# 2164_svf_breakout_planes_smd.net
KiCad netlist of a schematic drawn in EAGLE
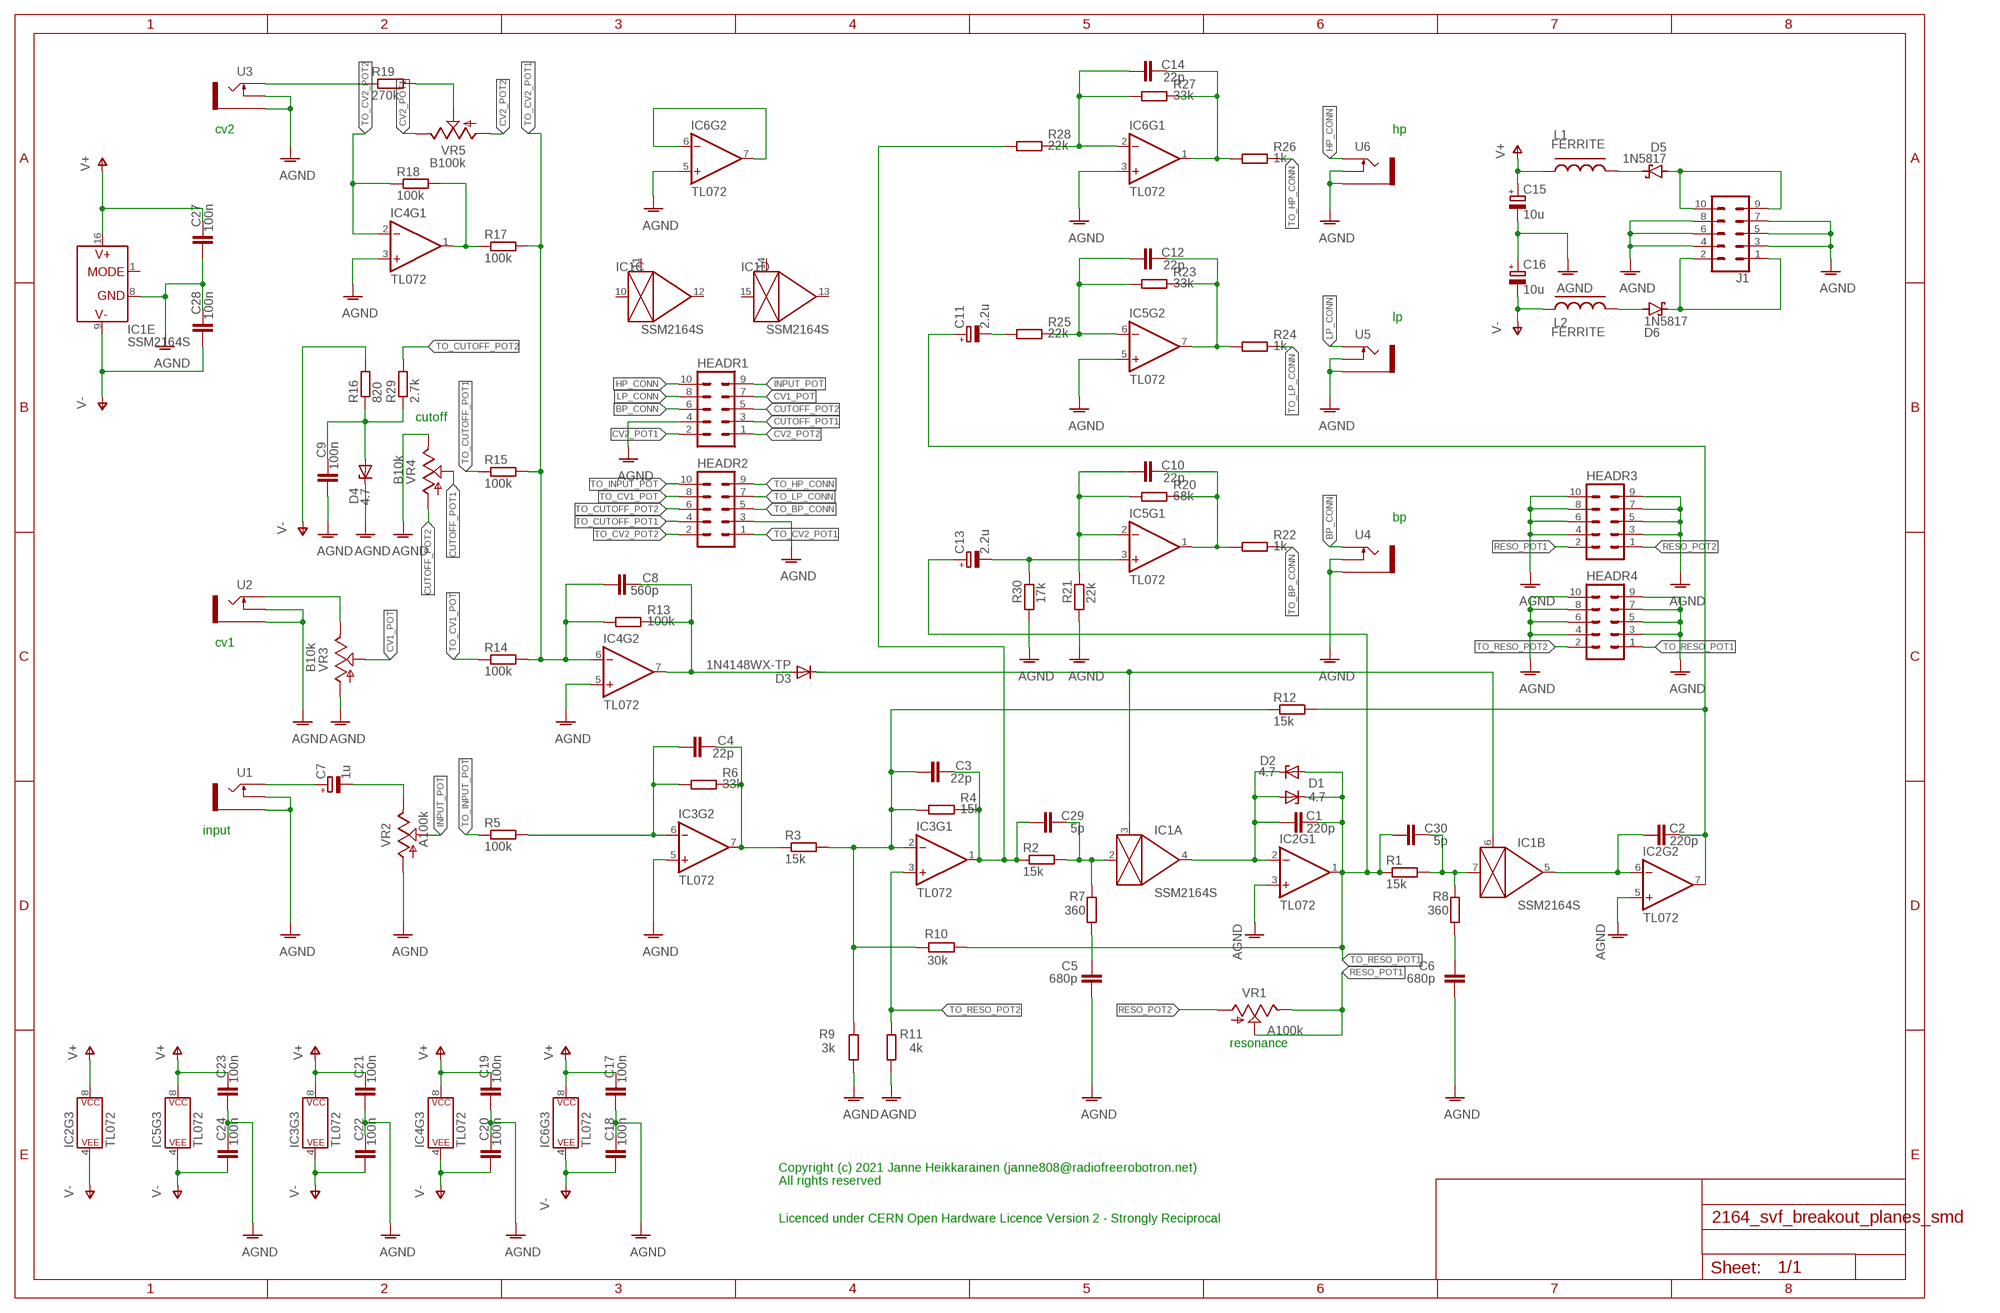
[diagram p0: schematic, sheet 1]

(export (version "E")
  (design (tool "Eeschema 10.0.6"))
  (components
    (comp (ref "C1")
      (value "220p")
      (footprint "eagle-import:C0603")
      (libsource (lib "eagle-import") (part "C-EUC0603"))
    )
    (comp (ref "C2")
      (value "220p")
      (footprint "eagle-import:C0603")
      (libsource (lib "eagle-import") (part "C-EUC0603"))
    )
    (comp (ref "C3")
      (value "22p")
      (footprint "eagle-import:C0603")
      (libsource (lib "eagle-import") (part "C-EUC0603"))
    )
    (comp (ref "C4")
      (value "22p")
      (footprint "eagle-import:C0603")
      (libsource (lib "eagle-import") (part "C-EUC0603"))
    )
    (comp (ref "C5")
      (value "680p")
      (footprint "eagle-import:C0603")
      (libsource (lib "eagle-import") (part "C-EUC0603"))
    )
    (comp (ref "C6")
      (value "680p")
      (footprint "eagle-import:C0603")
      (libsource (lib "eagle-import") (part "C-EUC0603"))
    )
    (comp (ref "C7")
      (value "1u")
      (footprint "eagle-import:PANASONIC_B")
      (libsource (lib "eagle-import") (part "CPOL-EUB"))
    )
    (comp (ref "C8")
      (value "560p")
      (footprint "eagle-import:C0603")
      (libsource (lib "eagle-import") (part "C-EUC0603"))
    )
    (comp (ref "C9")
      (value "100n")
      (footprint "eagle-import:C0603")
      (libsource (lib "eagle-import") (part "C-EUC0603"))
    )
    (comp (ref "C10")
      (value "22p")
      (footprint "eagle-import:C0603")
      (libsource (lib "eagle-import") (part "C-EUC0603"))
    )
    (comp (ref "C11")
      (value "2.2u")
      (footprint "eagle-import:PANASONIC_B")
      (libsource (lib "eagle-import") (part "CPOL-EUB"))
    )
    (comp (ref "C12")
      (value "22p")
      (footprint "eagle-import:C0603")
      (libsource (lib "eagle-import") (part "C-EUC0603"))
    )
    (comp (ref "C13")
      (value "2.2u")
      (footprint "eagle-import:PANASONIC_B")
      (libsource (lib "eagle-import") (part "CPOL-EUB"))
    )
    (comp (ref "C14")
      (value "22p")
      (footprint "eagle-import:C0603")
      (libsource (lib "eagle-import") (part "C-EUC0603"))
    )
    (comp (ref "C15")
      (value "10u")
      (footprint "eagle-import:PANASONIC_B")
      (libsource (lib "eagle-import") (part "CPOL-EUB"))
    )
    (comp (ref "C16")
      (value "10u")
      (footprint "eagle-import:PANASONIC_B")
      (libsource (lib "eagle-import") (part "CPOL-EUB"))
    )
    (comp (ref "C17")
      (value "100n")
      (footprint "eagle-import:C0603")
      (libsource (lib "eagle-import") (part "C-EUC0603"))
    )
    (comp (ref "C18")
      (value "100n")
      (footprint "eagle-import:C0603")
      (libsource (lib "eagle-import") (part "C-EUC0603"))
    )
    (comp (ref "C19")
      (value "100n")
      (footprint "eagle-import:C0603")
      (libsource (lib "eagle-import") (part "C-EUC0603"))
    )
    (comp (ref "C20")
      (value "100n")
      (footprint "eagle-import:C0603")
      (libsource (lib "eagle-import") (part "C-EUC0603"))
    )
    (comp (ref "C21")
      (value "100n")
      (footprint "eagle-import:C0603")
      (libsource (lib "eagle-import") (part "C-EUC0603"))
    )
    (comp (ref "C22")
      (value "100n")
      (footprint "eagle-import:C0603")
      (libsource (lib "eagle-import") (part "C-EUC0603"))
    )
    (comp (ref "C23")
      (value "100n")
      (footprint "eagle-import:C0603")
      (libsource (lib "eagle-import") (part "C-EUC0603"))
    )
    (comp (ref "C24")
      (value "100n")
      (footprint "eagle-import:C0603")
      (libsource (lib "eagle-import") (part "C-EUC0603"))
    )
    (comp (ref "C27")
      (value "100n")
      (footprint "eagle-import:C0603")
      (libsource (lib "eagle-import") (part "C-EUC0603"))
    )
    (comp (ref "C28")
      (value "100n")
      (footprint "eagle-import:C0603")
      (libsource (lib "eagle-import") (part "C-EUC0603"))
    )
    (comp (ref "C29")
      (value "5p")
      (footprint "eagle-import:C0603")
      (libsource (lib "eagle-import") (part "C-EUC0603"))
    )
    (comp (ref "C30")
      (value "5p")
      (footprint "eagle-import:C0603")
      (libsource (lib "eagle-import") (part "C-EUC0603"))
    )
    (comp (ref "D1")
      (value "4.7")
      (footprint "eagle-import:DIODE_SOD80C")
      (libsource (lib "eagle-import") (part "DIODE_ZENER-DIODESOD80C"))
    )
    (comp (ref "D2")
      (value "4.7")
      (footprint "eagle-import:DIODE_SOD80C")
      (libsource (lib "eagle-import") (part "DIODE_ZENER-DIODESOD80C"))
    )
    (comp (ref "D3")
      (value "1N4148WX-TP")
      (footprint "eagle-import:SOD323R-INFINEON")
      (libsource (lib "eagle-import") (part "1N4148WX-TP"))
    )
    (comp (ref "D4")
      (value "4.7")
      (footprint "eagle-import:DIODE_SOD80C")
      (libsource (lib "eagle-import") (part "DIODE_ZENER-DIODESOD80C"))
    )
    (comp (ref "D5")
      (value "1N5817")
      (footprint "eagle-import:DO35-7")
      (libsource (lib "eagle-import") (part "SCHOTTKY-DIODEDO35-7"))
    )
    (comp (ref "D6")
      (value "1N5817")
      (footprint "eagle-import:DO35-7")
      (libsource (lib "eagle-import") (part "SCHOTTKY-DIODEDO35-7"))
    )
    (comp (ref "HEADR1")
      (value "10PIN_BACKSIDE")
      (footprint "eagle-import:10PIN_BACKSIDE")
      (libsource (lib "eagle-import") (part "10PIN_BACKSIDE"))
    )
    (comp (ref "HEADR2")
      (value "10PIN_BACKSIDE")
      (footprint "eagle-import:10PIN_BACKSIDE")
      (libsource (lib "eagle-import") (part "10PIN_BACKSIDE"))
    )
    (comp (ref "HEADR3")
      (value "10PIN_BACKSIDE")
      (footprint "eagle-import:10PIN_BACKSIDE")
      (libsource (lib "eagle-import") (part "10PIN_BACKSIDE"))
    )
    (comp (ref "HEADR4")
      (value "10PIN_BACKSIDE")
      (footprint "eagle-import:10PIN_BACKSIDE")
      (libsource (lib "eagle-import") (part "10PIN_BACKSIDE"))
    )
    (comp (ref "IC1")
      (value "SSM2164S")
      (footprint "eagle-import:SOIC16N")
      (libsource (lib "eagle-import") (part "SSM2164S"))
    )
    (comp (ref "IC2")
      (value "TL072")
      (footprint "eagle-import:SO08")
      (libsource (lib "eagle-import") (part "OPAMP-DUALU"))
    )
    (comp (ref "IC3")
      (value "TL072")
      (footprint "eagle-import:SO08")
      (libsource (lib "eagle-import") (part "OPAMP-DUALU"))
    )
    (comp (ref "IC4")
      (value "TL072")
      (footprint "eagle-import:SO08")
      (libsource (lib "eagle-import") (part "OPAMP-DUALU"))
    )
    (comp (ref "IC5")
      (value "TL072")
      (footprint "eagle-import:SO08")
      (libsource (lib "eagle-import") (part "OPAMP-DUALU"))
    )
    (comp (ref "IC6")
      (value "TL072")
      (footprint "eagle-import:SO08")
      (libsource (lib "eagle-import") (part "OPAMP-DUALU"))
    )
    (comp (ref "J1")
      (value "CONN_05X2SHD")
      (footprint "eagle-import:2X5-SHROUDED")
      (libsource (lib "eagle-import") (part "CONN_05X2SHD"))
    )
    (comp (ref "L1")
      (value "FERRITE")
      (footprint "eagle-import:0603")
      (fields (field (name "PARTNO") "?"))
      (libsource (lib "eagle-import") (part "EXC3BP"))
    )
    (comp (ref "L2")
      (value "FERRITE")
      (footprint "eagle-import:0603")
      (fields (field (name "PARTNO") "?"))
      (libsource (lib "eagle-import") (part "EXC3BP"))
    )
    (comp (ref "R1")
      (value "15k")
      (footprint "eagle-import:R0603")
      (libsource (lib "eagle-import") (part "R-EU_R0603"))
    )
    (comp (ref "R2")
      (value "15k")
      (footprint "eagle-import:R0603")
      (libsource (lib "eagle-import") (part "R-EU_R0603"))
    )
    (comp (ref "R3")
      (value "15k")
      (footprint "eagle-import:R0603")
      (libsource (lib "eagle-import") (part "R-EU_R0603"))
    )
    (comp (ref "R4")
      (value "15k")
      (footprint "eagle-import:R0603")
      (libsource (lib "eagle-import") (part "R-EU_R0603"))
    )
    (comp (ref "R5")
      (value "100k")
      (footprint "eagle-import:R0603")
      (libsource (lib "eagle-import") (part "R-EU_R0603"))
    )
    (comp (ref "R6")
      (value "33k")
      (footprint "eagle-import:R0603")
      (libsource (lib "eagle-import") (part "R-EU_R0603"))
    )
    (comp (ref "R7")
      (value "360")
      (footprint "eagle-import:R0603")
      (libsource (lib "eagle-import") (part "R-EU_R0603"))
    )
    (comp (ref "R8")
      (value "360")
      (footprint "eagle-import:R0603")
      (libsource (lib "eagle-import") (part "R-EU_R0603"))
    )
    (comp (ref "R9")
      (value "3k")
      (footprint "eagle-import:R0603")
      (libsource (lib "eagle-import") (part "R-EU_R0603"))
    )
    (comp (ref "R10")
      (value "30k")
      (footprint "eagle-import:R0603")
      (libsource (lib "eagle-import") (part "R-EU_R0603"))
    )
    (comp (ref "R11")
      (value "4k")
      (footprint "eagle-import:R0603")
      (libsource (lib "eagle-import") (part "R-EU_R0603"))
    )
    (comp (ref "R12")
      (value "15k")
      (footprint "eagle-import:R0603")
      (libsource (lib "eagle-import") (part "R-EU_R0603"))
    )
    (comp (ref "R13")
      (value "100k")
      (footprint "eagle-import:R0603")
      (libsource (lib "eagle-import") (part "R-EU_R0603"))
    )
    (comp (ref "R14")
      (value "100k")
      (footprint "eagle-import:R0603")
      (libsource (lib "eagle-import") (part "R-EU_R0603"))
    )
    (comp (ref "R15")
      (value "100k")
      (footprint "eagle-import:R0603")
      (libsource (lib "eagle-import") (part "R-EU_R0603"))
    )
    (comp (ref "R16")
      (value "820")
      (footprint "eagle-import:R0603")
      (libsource (lib "eagle-import") (part "R-EU_R0603"))
    )
    (comp (ref "R17")
      (value "100k")
      (footprint "eagle-import:R0603")
      (libsource (lib "eagle-import") (part "R-EU_R0603"))
    )
    (comp (ref "R18")
      (value "100k")
      (footprint "eagle-import:R0603")
      (libsource (lib "eagle-import") (part "R-EU_R0603"))
    )
    (comp (ref "R19")
      (value "270k")
      (footprint "eagle-import:R0603")
      (libsource (lib "eagle-import") (part "R-EU_R0603"))
    )
    (comp (ref "R20")
      (value "68k")
      (footprint "eagle-import:R0603")
      (libsource (lib "eagle-import") (part "R-EU_R0603"))
    )
    (comp (ref "R21")
      (value "22k")
      (footprint "eagle-import:R0603")
      (libsource (lib "eagle-import") (part "R-EU_R0603"))
    )
    (comp (ref "R22")
      (value "1k")
      (footprint "eagle-import:R0603")
      (libsource (lib "eagle-import") (part "R-EU_R0603"))
    )
    (comp (ref "R23")
      (value "33k")
      (footprint "eagle-import:R0603")
      (libsource (lib "eagle-import") (part "R-EU_R0603"))
    )
    (comp (ref "R24")
      (value "1k")
      (footprint "eagle-import:R0603")
      (libsource (lib "eagle-import") (part "R-EU_R0603"))
    )
    (comp (ref "R25")
      (value "22k")
      (footprint "eagle-import:R0603")
      (libsource (lib "eagle-import") (part "R-EU_R0603"))
    )
    (comp (ref "R26")
      (value "1k")
      (footprint "eagle-import:R0603")
      (libsource (lib "eagle-import") (part "R-EU_R0603"))
    )
    (comp (ref "R27")
      (value "33k")
      (footprint "eagle-import:R0603")
      (libsource (lib "eagle-import") (part "R-EU_R0603"))
    )
    (comp (ref "R28")
      (value "22k")
      (footprint "eagle-import:R0603")
      (libsource (lib "eagle-import") (part "R-EU_R0603"))
    )
    (comp (ref "R29")
      (value "2.7k")
      (footprint "eagle-import:R0603")
      (libsource (lib "eagle-import") (part "R-EU_R0603"))
    )
    (comp (ref "R30")
      (value "17k")
      (footprint "eagle-import:R0603")
      (libsource (lib "eagle-import") (part "R-EU_R0603"))
    )
    (comp (ref "U1")
      (value "THONKICONNNEW")
      (footprint "eagle-import:WQP-PJ301M-12_JACK")
      (libsource (lib "eagle-import") (part "THONKICONNNEW"))
    )
    (comp (ref "U2")
      (value "THONKICONNNEW")
      (footprint "eagle-import:WQP-PJ301M-12_JACK")
      (libsource (lib "eagle-import") (part "THONKICONNNEW"))
    )
    (comp (ref "U3")
      (value "THONKICONNNEW")
      (footprint "eagle-import:WQP-PJ301M-12_JACK")
      (libsource (lib "eagle-import") (part "THONKICONNNEW"))
    )
    (comp (ref "U4")
      (value "THONKICONNNEW")
      (footprint "eagle-import:WQP-PJ301M-12_JACK")
      (libsource (lib "eagle-import") (part "THONKICONNNEW"))
    )
    (comp (ref "U5")
      (value "THONKICONNNEW")
      (footprint "eagle-import:WQP-PJ301M-12_JACK")
      (libsource (lib "eagle-import") (part "THONKICONNNEW"))
    )
    (comp (ref "U6")
      (value "THONKICONNNEW")
      (footprint "eagle-import:WQP-PJ301M-12_JACK")
      (libsource (lib "eagle-import") (part "THONKICONNNEW"))
    )
    (comp (ref "VR1")
      (value "A100k")
      (footprint "eagle-import:9MM_SNAP-IN_POT")
      (libsource (lib "eagle-import") (part "9MM_SNAP-IN_POT_"))
    )
    (comp (ref "VR2")
      (value "A100k")
      (footprint "eagle-import:9MM_SNAP-IN_POT")
      (libsource (lib "eagle-import") (part "9MM_SNAP-IN_POT_"))
    )
    (comp (ref "VR3")
      (value "B10k")
      (footprint "eagle-import:9MM_SNAP-IN_POT")
      (libsource (lib "eagle-import") (part "9MM_SNAP-IN_POT_"))
    )
    (comp (ref "VR4")
      (value "B10k")
      (footprint "eagle-import:9MM_SNAP-IN_POT")
      (libsource (lib "eagle-import") (part "9MM_SNAP-IN_POT_"))
    )
    (comp (ref "VR5")
      (value "B100k")
      (footprint "eagle-import:9MM_SNAP-IN_POT")
      (libsource (lib "eagle-import") (part "9MM_SNAP-IN_POT_"))
    )
  )
  (nets
    (net (code "1") (name "AGND") (class "Default")
      (node (ref "C15") (pin "-") (pinfunction "-_-") (pintype "passive"))
      (node (ref "C16") (pin "+") (pinfunction "+_+") (pintype "passive"))
      (node (ref "C17") (pin "1") (pinfunction "1_1") (pintype "passive"))
      (node (ref "C18") (pin "2") (pinfunction "2_2") (pintype "passive"))
      (node (ref "C19") (pin "1") (pinfunction "1_1") (pintype "passive"))
      (node (ref "C20") (pin "2") (pinfunction "2_2") (pintype "passive"))
      (node (ref "C21") (pin "1") (pinfunction "1_1") (pintype "passive"))
      (node (ref "C22") (pin "2") (pinfunction "2_2") (pintype "passive"))
      (node (ref "C23") (pin "1") (pinfunction "1_1") (pintype "passive"))
      (node (ref "C24") (pin "2") (pinfunction "2_2") (pintype "passive"))
      (node (ref "C27") (pin "1") (pinfunction "1_1") (pintype "passive"))
      (node (ref "C28") (pin "2") (pinfunction "2_2") (pintype "passive"))
      (node (ref "C5") (pin "1") (pinfunction "1_1") (pintype "passive"))
      (node (ref "C6") (pin "1") (pinfunction "1_1") (pintype "passive"))
      (node (ref "C9") (pin "1") (pinfunction "1_1") (pintype "passive"))
      (node (ref "D4") (pin "C") (pinfunction "C_C") (pintype "passive"))
      (node (ref "HEADR1") (pin "4") (pinfunction "4_4") (pintype "passive"))
      (node (ref "HEADR2") (pin "3") (pinfunction "3_3") (pintype "passive"))
      (node (ref "HEADR3") (pin "10") (pinfunction "10_10") (pintype "passive"))
      (node (ref "HEADR3") (pin "3") (pinfunction "3_3") (pintype "passive"))
      (node (ref "HEADR3") (pin "4") (pinfunction "4_4") (pintype "passive"))
      (node (ref "HEADR3") (pin "5") (pinfunction "5_5") (pintype "passive"))
      (node (ref "HEADR3") (pin "6") (pinfunction "6_6") (pintype "passive"))
      (node (ref "HEADR3") (pin "7") (pinfunction "7_7") (pintype "passive"))
      (node (ref "HEADR3") (pin "8") (pinfunction "8_8") (pintype "passive"))
      (node (ref "HEADR3") (pin "9") (pinfunction "9_9") (pintype "passive"))
      (node (ref "HEADR4") (pin "10") (pinfunction "10_10") (pintype "passive"))
      (node (ref "HEADR4") (pin "3") (pinfunction "3_3") (pintype "passive"))
      (node (ref "HEADR4") (pin "4") (pinfunction "4_4") (pintype "passive"))
      (node (ref "HEADR4") (pin "5") (pinfunction "5_5") (pintype "passive"))
      (node (ref "HEADR4") (pin "6") (pinfunction "6_6") (pintype "passive"))
      (node (ref "HEADR4") (pin "7") (pinfunction "7_7") (pintype "passive"))
      (node (ref "HEADR4") (pin "8") (pinfunction "8_8") (pintype "passive"))
      (node (ref "HEADR4") (pin "9") (pinfunction "9_9") (pintype "passive"))
      (node (ref "IC1") (pin "8") (pinfunction "GND_8") (pintype "power_in"))
      (node (ref "IC2") (pin "3") (pinfunction "+IN_3") (pintype "input"))
      (node (ref "IC2") (pin "5") (pinfunction "+IN_5") (pintype "input"))
      (node (ref "IC3") (pin "5") (pinfunction "+IN_5") (pintype "input"))
      (node (ref "IC4") (pin "3") (pinfunction "+IN_3") (pintype "input"))
      (node (ref "IC4") (pin "5") (pinfunction "+IN_5") (pintype "input"))
      (node (ref "IC5") (pin "5") (pinfunction "+IN_5") (pintype "input"))
      (node (ref "IC6") (pin "3") (pinfunction "+IN_3") (pintype "input"))
      (node (ref "IC6") (pin "5") (pinfunction "+IN_5") (pintype "input"))
      (node (ref "J1") (pin "3") (pinfunction "3_3") (pintype "passive"))
      (node (ref "J1") (pin "4") (pinfunction "4_4") (pintype "passive"))
      (node (ref "J1") (pin "5") (pinfunction "5_5") (pintype "passive"))
      (node (ref "J1") (pin "6") (pinfunction "6_6") (pintype "passive"))
      (node (ref "J1") (pin "7") (pinfunction "7_7") (pintype "passive"))
      (node (ref "J1") (pin "8") (pinfunction "8_8") (pintype "passive"))
      (node (ref "R11") (pin "1") (pinfunction "1_1") (pintype "passive"))
      (node (ref "R21") (pin "1") (pinfunction "1_1") (pintype "passive"))
      (node (ref "R30") (pin "1") (pinfunction "1_1") (pintype "passive"))
      (node (ref "R9") (pin "1") (pinfunction "1_1") (pintype "passive"))
      (node (ref "U1") (pin "P$2_SWITCH") (pinfunction "SWITCH_P$2_SWITCH") (pintype "passive"))
      (node (ref "U1") (pin "P$3_SLEEVE") (pinfunction "SLEEVE_P$3_SLEEVE") (pintype "passive"))
      (node (ref "U2") (pin "P$2_SWITCH") (pinfunction "SWITCH_P$2_SWITCH") (pintype "passive"))
      (node (ref "U2") (pin "P$3_SLEEVE") (pinfunction "SLEEVE_P$3_SLEEVE") (pintype "passive"))
      (node (ref "U3") (pin "P$2_SWITCH") (pinfunction "SWITCH_P$2_SWITCH") (pintype "passive"))
      (node (ref "U3") (pin "P$3_SLEEVE") (pinfunction "SLEEVE_P$3_SLEEVE") (pintype "passive"))
      (node (ref "U4") (pin "P$2_SWITCH") (pinfunction "SWITCH_P$2_SWITCH") (pintype "passive"))
      (node (ref "U4") (pin "P$3_SLEEVE") (pinfunction "SLEEVE_P$3_SLEEVE") (pintype "passive"))
      (node (ref "U5") (pin "P$2_SWITCH") (pinfunction "SWITCH_P$2_SWITCH") (pintype "passive"))
      (node (ref "U5") (pin "P$3_SLEEVE") (pinfunction "SLEEVE_P$3_SLEEVE") (pintype "passive"))
      (node (ref "U6") (pin "P$2_SWITCH") (pinfunction "SWITCH_P$2_SWITCH") (pintype "passive"))
      (node (ref "U6") (pin "P$3_SLEEVE") (pinfunction "SLEEVE_P$3_SLEEVE") (pintype "passive"))
      (node (ref "VR2") (pin "1") (pinfunction "A_1") (pintype "passive"))
      (node (ref "VR3") (pin "1") (pinfunction "A_1") (pintype "passive"))
      (node (ref "VR4") (pin "3") (pinfunction "E_3") (pintype "passive"))
    )
    (net (code "2") (name "BP_CONN") (class "Default")
      (node (ref "HEADR1") (pin "6") (pinfunction "6_6") (pintype "passive"))
      (node (ref "U4") (pin "P$1_TIP") (pinfunction "TIP_P$1_TIP") (pintype "passive"))
    )
    (net (code "3") (name "CUTOFF_POT1") (class "Default")
      (node (ref "HEADR1") (pin "3") (pinfunction "3_3") (pintype "passive"))
      (node (ref "VR4") (pin "2") (pinfunction "S_2") (pintype "passive"))
    )
    (net (code "4") (name "CUTOFF_POT2") (class "Default")
      (node (ref "HEADR1") (pin "5") (pinfunction "5_5") (pintype "passive"))
      (node (ref "VR4") (pin "1") (pinfunction "A_1") (pintype "passive"))
    )
    (net (code "5") (name "CV1_POT") (class "Default")
      (node (ref "HEADR1") (pin "7") (pinfunction "7_7") (pintype "passive"))
      (node (ref "VR3") (pin "2") (pinfunction "S_2") (pintype "passive"))
    )
    (net (code "6") (name "CV2_POT1") (class "Default")
      (node (ref "HEADR1") (pin "2") (pinfunction "2_2") (pintype "passive"))
      (node (ref "VR5") (pin "3") (pinfunction "E_3") (pintype "passive"))
    )
    (net (code "7") (name "CV2_POT2") (class "Default")
      (node (ref "HEADR1") (pin "1") (pinfunction "1_1") (pintype "passive"))
      (node (ref "VR5") (pin "1") (pinfunction "A_1") (pintype "passive"))
    )
    (net (code "8") (name "HP_CONN") (class "Default")
      (node (ref "HEADR1") (pin "10") (pinfunction "10_10") (pintype "passive"))
      (node (ref "U6") (pin "P$1_TIP") (pinfunction "TIP_P$1_TIP") (pintype "passive"))
    )
    (net (code "9") (name "INPUT_POT") (class "Default")
      (node (ref "HEADR1") (pin "9") (pinfunction "9_9") (pintype "passive"))
      (node (ref "VR2") (pin "2") (pinfunction "S_2") (pintype "passive"))
    )
    (net (code "10") (name "LP_CONN") (class "Default")
      (node (ref "HEADR1") (pin "8") (pinfunction "8_8") (pintype "passive"))
      (node (ref "U5") (pin "P$1_TIP") (pinfunction "TIP_P$1_TIP") (pintype "passive"))
    )
    (net (code "11") (name "Net-(C5-Pad2)") (class "Default")
      (node (ref "C5") (pin "2") (pinfunction "2_2") (pintype "passive"))
      (node (ref "R7") (pin "1") (pinfunction "1_1") (pintype "passive"))
    )
    (net (code "12") (name "Net-(C6-Pad2)") (class "Default")
      (node (ref "C6") (pin "2") (pinfunction "2_2") (pintype "passive"))
      (node (ref "R8") (pin "1") (pinfunction "1_1") (pintype "passive"))
    )
    (net (code "13") (name "Net-(C9-Pad2)") (class "Default")
      (node (ref "C9") (pin "2") (pinfunction "2_2") (pintype "passive"))
      (node (ref "D4") (pin "A") (pinfunction "A_A") (pintype "passive"))
      (node (ref "R16") (pin "1") (pinfunction "1_1") (pintype "passive"))
      (node (ref "R29") (pin "1") (pinfunction "1_1") (pintype "passive"))
    )
    (net (code "14") (name "Net-(C11-Pad-)") (class "Default")
      (node (ref "C11") (pin "-") (pinfunction "-_-") (pintype "passive"))
      (node (ref "R25") (pin "1") (pinfunction "1_1") (pintype "passive"))
    )
    (net (code "15") (name "Net-(D5-PadA)") (class "Default")
      (node (ref "D5") (pin "A") (pinfunction "A_A") (pintype "passive"))
      (node (ref "J1") (pin "10") (pinfunction "10_10") (pintype "passive"))
      (node (ref "J1") (pin "9") (pinfunction "9_9") (pintype "passive"))
    )
    (net (code "16") (name "Net-(D5-PadC)") (class "Default")
      (node (ref "D5") (pin "C") (pinfunction "C_C") (pintype "passive"))
      (node (ref "L1") (pin "2") (pinfunction "2_2") (pintype "passive"))
    )
    (net (code "17") (name "Net-(D6-PadA)") (class "Default")
      (node (ref "D6") (pin "A") (pinfunction "A_A") (pintype "passive"))
      (node (ref "L2") (pin "2") (pinfunction "2_2") (pintype "passive"))
    )
    (net (code "18") (name "Net-(D6-PadC)") (class "Default")
      (node (ref "D6") (pin "C") (pinfunction "C_C") (pintype "passive"))
      (node (ref "J1") (pin "1") (pinfunction "1_1") (pintype "passive"))
      (node (ref "J1") (pin "2") (pinfunction "2_2") (pintype "passive"))
    )
    (net (code "19") (name "Net-(IC1A-CTRL)") (class "Default")
      (node (ref "D3") (pin "C") (pinfunction "C_C") (pintype "passive"))
      (node (ref "IC1") (pin "3") (pinfunction "CTRL_3") (pintype "input"))
      (node (ref "IC1") (pin "6") (pinfunction "CTRL_6") (pintype "input"))
    )
    (net (code "20") (name "Net-(IC1A-IN)") (class "Default")
      (node (ref "C29") (pin "2") (pinfunction "2_2") (pintype "passive"))
      (node (ref "IC1") (pin "2") (pinfunction "IN_2") (pintype "input"))
      (node (ref "R2") (pin "2") (pinfunction "2_2") (pintype "passive"))
      (node (ref "R7") (pin "2") (pinfunction "2_2") (pintype "passive"))
    )
    (net (code "21") (name "Net-(IC1A-OUT)") (class "Default")
      (node (ref "C1") (pin "1") (pinfunction "1_1") (pintype "passive"))
      (node (ref "D1") (pin "A") (pinfunction "A_A") (pintype "passive"))
      (node (ref "D2") (pin "C") (pinfunction "C_C") (pintype "passive"))
      (node (ref "IC1") (pin "4") (pinfunction "OUT_4") (pintype "output"))
      (node (ref "IC2") (pin "2") (pinfunction "-IN_2") (pintype "input"))
    )
    (net (code "22") (name "Net-(IC1B-IN)") (class "Default")
      (node (ref "C30") (pin "2") (pinfunction "2_2") (pintype "passive"))
      (node (ref "IC1") (pin "7") (pinfunction "IN_7") (pintype "input"))
      (node (ref "R1") (pin "2") (pinfunction "2_2") (pintype "passive"))
      (node (ref "R8") (pin "2") (pinfunction "2_2") (pintype "passive"))
    )
    (net (code "23") (name "Net-(IC1B-OUT)") (class "Default")
      (node (ref "C2") (pin "1") (pinfunction "1_1") (pintype "passive"))
      (node (ref "IC1") (pin "5") (pinfunction "OUT_5") (pintype "output"))
      (node (ref "IC2") (pin "6") (pinfunction "-IN_6") (pintype "input"))
    )
    (net (code "24") (name "Net-(IC2B-OUT)") (class "Default")
      (node (ref "C11") (pin "+") (pinfunction "+_+") (pintype "passive"))
      (node (ref "C2") (pin "2") (pinfunction "2_2") (pintype "passive"))
      (node (ref "IC2") (pin "7") (pinfunction "OUT_7") (pintype "output"))
      (node (ref "R12") (pin "2") (pinfunction "2_2") (pintype "passive"))
    )
    (net (code "25") (name "Net-(IC3A--IN)") (class "Default")
      (node (ref "C3") (pin "1") (pinfunction "1_1") (pintype "passive"))
      (node (ref "IC3") (pin "2") (pinfunction "-IN_2") (pintype "input"))
      (node (ref "R10") (pin "2") (pinfunction "2_2") (pintype "passive"))
      (node (ref "R12") (pin "1") (pinfunction "1_1") (pintype "passive"))
      (node (ref "R3") (pin "2") (pinfunction "2_2") (pintype "passive"))
      (node (ref "R4") (pin "1") (pinfunction "1_1") (pintype "passive"))
      (node (ref "R9") (pin "2") (pinfunction "2_2") (pintype "passive"))
    )
    (net (code "26") (name "Net-(IC3A-OUT)") (class "Default")
      (node (ref "C29") (pin "1") (pinfunction "1_1") (pintype "passive"))
      (node (ref "C3") (pin "2") (pinfunction "2_2") (pintype "passive"))
      (node (ref "IC3") (pin "1") (pinfunction "OUT_1") (pintype "output"))
      (node (ref "R2") (pin "1") (pinfunction "1_1") (pintype "passive"))
      (node (ref "R28") (pin "1") (pinfunction "1_1") (pintype "passive"))
      (node (ref "R4") (pin "2") (pinfunction "2_2") (pintype "passive"))
    )
    (net (code "27") (name "Net-(IC3B--IN)") (class "Default")
      (node (ref "C4") (pin "1") (pinfunction "1_1") (pintype "passive"))
      (node (ref "IC3") (pin "6") (pinfunction "-IN_6") (pintype "input"))
      (node (ref "R5") (pin "2") (pinfunction "2_2") (pintype "passive"))
      (node (ref "R6") (pin "1") (pinfunction "1_1") (pintype "passive"))
    )
    (net (code "28") (name "Net-(IC3B-OUT)") (class "Default")
      (node (ref "C4") (pin "2") (pinfunction "2_2") (pintype "passive"))
      (node (ref "IC3") (pin "7") (pinfunction "OUT_7") (pintype "output"))
      (node (ref "R3") (pin "1") (pinfunction "1_1") (pintype "passive"))
      (node (ref "R6") (pin "2") (pinfunction "2_2") (pintype "passive"))
    )
    (net (code "29") (name "Net-(IC4A-OUT)") (class "Default")
      (node (ref "IC4") (pin "1") (pinfunction "OUT_1") (pintype "output"))
      (node (ref "R17") (pin "1") (pinfunction "1_1") (pintype "passive"))
      (node (ref "R18") (pin "2") (pinfunction "2_2") (pintype "passive"))
    )
    (net (code "30") (name "Net-(IC4B-OUT)") (class "Default")
      (node (ref "C8") (pin "2") (pinfunction "2_2") (pintype "passive"))
      (node (ref "D3") (pin "A") (pinfunction "A_A") (pintype "passive"))
      (node (ref "IC4") (pin "7") (pinfunction "OUT_7") (pintype "output"))
      (node (ref "R13") (pin "2") (pinfunction "2_2") (pintype "passive"))
    )
    (net (code "31") (name "Net-(IC5A-+IN)") (class "Default")
      (node (ref "C13") (pin "-") (pinfunction "-_-") (pintype "passive"))
      (node (ref "IC5") (pin "3") (pinfunction "+IN_3") (pintype "input"))
      (node (ref "R30") (pin "2") (pinfunction "2_2") (pintype "passive"))
    )
    (net (code "32") (name "Net-(IC5A--IN)") (class "Default")
      (node (ref "C10") (pin "1") (pinfunction "1_1") (pintype "passive"))
      (node (ref "IC5") (pin "2") (pinfunction "-IN_2") (pintype "input"))
      (node (ref "R20") (pin "1") (pinfunction "1_1") (pintype "passive"))
      (node (ref "R21") (pin "2") (pinfunction "2_2") (pintype "passive"))
    )
    (net (code "33") (name "Net-(IC5A-OUT)") (class "Default")
      (node (ref "C10") (pin "2") (pinfunction "2_2") (pintype "passive"))
      (node (ref "IC5") (pin "1") (pinfunction "OUT_1") (pintype "output"))
      (node (ref "R20") (pin "2") (pinfunction "2_2") (pintype "passive"))
      (node (ref "R22") (pin "1") (pinfunction "1_1") (pintype "passive"))
    )
    (net (code "34") (name "Net-(IC5B--IN)") (class "Default")
      (node (ref "C12") (pin "1") (pinfunction "1_1") (pintype "passive"))
      (node (ref "IC5") (pin "6") (pinfunction "-IN_6") (pintype "input"))
      (node (ref "R23") (pin "1") (pinfunction "1_1") (pintype "passive"))
      (node (ref "R25") (pin "2") (pinfunction "2_2") (pintype "passive"))
    )
    (net (code "35") (name "Net-(IC5B-OUT)") (class "Default")
      (node (ref "C12") (pin "2") (pinfunction "2_2") (pintype "passive"))
      (node (ref "IC5") (pin "7") (pinfunction "OUT_7") (pintype "output"))
      (node (ref "R23") (pin "2") (pinfunction "2_2") (pintype "passive"))
      (node (ref "R24") (pin "1") (pinfunction "1_1") (pintype "passive"))
    )
    (net (code "36") (name "Net-(IC6A--IN)") (class "Default")
      (node (ref "C14") (pin "1") (pinfunction "1_1") (pintype "passive"))
      (node (ref "IC6") (pin "2") (pinfunction "-IN_2") (pintype "input"))
      (node (ref "R27") (pin "1") (pinfunction "1_1") (pintype "passive"))
      (node (ref "R28") (pin "2") (pinfunction "2_2") (pintype "passive"))
    )
    (net (code "37") (name "Net-(IC6A-OUT)") (class "Default")
      (node (ref "C14") (pin "2") (pinfunction "2_2") (pintype "passive"))
      (node (ref "IC6") (pin "1") (pinfunction "OUT_1") (pintype "output"))
      (node (ref "R26") (pin "1") (pinfunction "1_1") (pintype "passive"))
      (node (ref "R27") (pin "2") (pinfunction "2_2") (pintype "passive"))
    )
    (net (code "38") (name "Net-(IC6B--IN)") (class "Default")
      (node (ref "IC6") (pin "6") (pinfunction "-IN_6") (pintype "input"))
      (node (ref "IC6") (pin "7") (pinfunction "OUT_7") (pintype "output"))
    )
    (net (code "39") (name "Net-(U1-TIP)") (class "Default")
      (node (ref "C7") (pin "+") (pinfunction "+_+") (pintype "passive"))
      (node (ref "U1") (pin "P$1_TIP") (pinfunction "TIP_P$1_TIP") (pintype "passive"))
    )
    (net (code "40") (name "Net-(U2-TIP)") (class "Default")
      (node (ref "U2") (pin "P$1_TIP") (pinfunction "TIP_P$1_TIP") (pintype "passive"))
      (node (ref "VR3") (pin "3") (pinfunction "E_3") (pintype "passive"))
    )
    (net (code "41") (name "Net-(U3-TIP)") (class "Default")
      (node (ref "R19") (pin "1") (pinfunction "1_1") (pintype "passive"))
      (node (ref "U3") (pin "P$1_TIP") (pinfunction "TIP_P$1_TIP") (pintype "passive"))
    )
    (net (code "42") (name "Net-(VR2-E)") (class "Default")
      (node (ref "C7") (pin "-") (pinfunction "-_-") (pintype "passive"))
      (node (ref "VR2") (pin "3") (pinfunction "E_3") (pintype "passive"))
    )
    (net (code "43") (name "Net-(VR5-S)") (class "Default")
      (node (ref "R19") (pin "2") (pinfunction "2_2") (pintype "passive"))
      (node (ref "VR5") (pin "2") (pinfunction "S_2") (pintype "passive"))
    )
    (net (code "44") (name "RESO_POT1") (class "Default")
      (node (ref "HEADR3") (pin "2") (pinfunction "2_2") (pintype "passive"))
      (node (ref "VR1") (pin "2") (pinfunction "S_2") (pintype "passive"))
      (node (ref "VR1") (pin "3") (pinfunction "E_3") (pintype "passive"))
    )
    (net (code "45") (name "RESO_POT2") (class "Default")
      (node (ref "HEADR3") (pin "1") (pinfunction "1_1") (pintype "passive"))
      (node (ref "VR1") (pin "1") (pinfunction "A_1") (pintype "passive"))
    )
    (net (code "46") (name "TO_BP_CONN") (class "Default")
      (node (ref "HEADR2") (pin "5") (pinfunction "5_5") (pintype "passive"))
      (node (ref "R22") (pin "2") (pinfunction "2_2") (pintype "passive"))
    )
    (net (code "47") (name "TO_CUTOFF_POT1") (class "Default")
      (node (ref "HEADR2") (pin "4") (pinfunction "4_4") (pintype "passive"))
      (node (ref "R15") (pin "1") (pinfunction "1_1") (pintype "passive"))
    )
    (net (code "48") (name "TO_CUTOFF_POT2") (class "Default")
      (node (ref "HEADR2") (pin "6") (pinfunction "6_6") (pintype "passive"))
      (node (ref "R29") (pin "2") (pinfunction "2_2") (pintype "passive"))
    )
    (net (code "49") (name "TO_CV1_POT") (class "Default")
      (node (ref "HEADR2") (pin "8") (pinfunction "8_8") (pintype "passive"))
      (node (ref "R14") (pin "1") (pinfunction "1_1") (pintype "passive"))
    )
    (net (code "50") (name "TO_CV2_POT1") (class "Default")
      (node (ref "C8") (pin "1") (pinfunction "1_1") (pintype "passive"))
      (node (ref "HEADR2") (pin "1") (pinfunction "1_1") (pintype "passive"))
      (node (ref "IC4") (pin "6") (pinfunction "-IN_6") (pintype "input"))
      (node (ref "R13") (pin "1") (pinfunction "1_1") (pintype "passive"))
      (node (ref "R14") (pin "2") (pinfunction "2_2") (pintype "passive"))
      (node (ref "R15") (pin "2") (pinfunction "2_2") (pintype "passive"))
      (node (ref "R17") (pin "2") (pinfunction "2_2") (pintype "passive"))
    )
    (net (code "51") (name "TO_CV2_POT2") (class "Default")
      (node (ref "HEADR2") (pin "2") (pinfunction "2_2") (pintype "passive"))
      (node (ref "IC4") (pin "2") (pinfunction "-IN_2") (pintype "input"))
      (node (ref "R18") (pin "1") (pinfunction "1_1") (pintype "passive"))
    )
    (net (code "52") (name "TO_HP_CONN") (class "Default")
      (node (ref "HEADR2") (pin "9") (pinfunction "9_9") (pintype "passive"))
      (node (ref "R26") (pin "2") (pinfunction "2_2") (pintype "passive"))
    )
    (net (code "53") (name "TO_INPUT_POT") (class "Default")
      (node (ref "HEADR2") (pin "10") (pinfunction "10_10") (pintype "passive"))
      (node (ref "R5") (pin "1") (pinfunction "1_1") (pintype "passive"))
    )
    (net (code "54") (name "TO_LP_CONN") (class "Default")
      (node (ref "HEADR2") (pin "7") (pinfunction "7_7") (pintype "passive"))
      (node (ref "R24") (pin "2") (pinfunction "2_2") (pintype "passive"))
    )
    (net (code "55") (name "TO_RESO_POT1") (class "Default")
      (node (ref "C1") (pin "2") (pinfunction "2_2") (pintype "passive"))
      (node (ref "C13") (pin "+") (pinfunction "+_+") (pintype "passive"))
      (node (ref "C30") (pin "1") (pinfunction "1_1") (pintype "passive"))
      (node (ref "D1") (pin "C") (pinfunction "C_C") (pintype "passive"))
      (node (ref "D2") (pin "A") (pinfunction "A_A") (pintype "passive"))
      (node (ref "HEADR4") (pin "1") (pinfunction "1_1") (pintype "passive"))
      (node (ref "IC2") (pin "1") (pinfunction "OUT_1") (pintype "output"))
      (node (ref "R1") (pin "1") (pinfunction "1_1") (pintype "passive"))
      (node (ref "R10") (pin "1") (pinfunction "1_1") (pintype "passive"))
    )
    (net (code "56") (name "TO_RESO_POT2") (class "Default")
      (node (ref "HEADR4") (pin "2") (pinfunction "2_2") (pintype "passive"))
      (node (ref "IC3") (pin "3") (pinfunction "+IN_3") (pintype "input"))
      (node (ref "R11") (pin "2") (pinfunction "2_2") (pintype "passive"))
    )
    (net (code "57") (name "V+") (class "Default")
      (node (ref "C15") (pin "+") (pinfunction "+_+") (pintype "passive"))
      (node (ref "C17") (pin "2") (pinfunction "2_2") (pintype "passive"))
      (node (ref "C19") (pin "2") (pinfunction "2_2") (pintype "passive"))
      (node (ref "C21") (pin "2") (pinfunction "2_2") (pintype "passive"))
      (node (ref "C23") (pin "2") (pinfunction "2_2") (pintype "passive"))
      (node (ref "C27") (pin "2") (pinfunction "2_2") (pintype "passive"))
      (node (ref "IC1") (pin "16") (pinfunction "V+_16") (pintype "power_in"))
      (node (ref "IC2") (pin "8") (pinfunction "P$V+_8") (pintype "bidirectional"))
      (node (ref "IC3") (pin "8") (pinfunction "P$V+_8") (pintype "bidirectional"))
      (node (ref "IC4") (pin "8") (pinfunction "P$V+_8") (pintype "bidirectional"))
      (node (ref "IC5") (pin "8") (pinfunction "P$V+_8") (pintype "bidirectional"))
      (node (ref "IC6") (pin "8") (pinfunction "P$V+_8") (pintype "bidirectional"))
      (node (ref "L1") (pin "1") (pinfunction "1_1") (pintype "passive"))
    )
    (net (code "58") (name "V-") (class "Default")
      (node (ref "C16") (pin "-") (pinfunction "-_-") (pintype "passive"))
      (node (ref "C18") (pin "1") (pinfunction "1_1") (pintype "passive"))
      (node (ref "C20") (pin "1") (pinfunction "1_1") (pintype "passive"))
      (node (ref "C22") (pin "1") (pinfunction "1_1") (pintype "passive"))
      (node (ref "C24") (pin "1") (pinfunction "1_1") (pintype "passive"))
      (node (ref "C28") (pin "1") (pinfunction "1_1") (pintype "passive"))
      (node (ref "IC1") (pin "9") (pinfunction "V-_9") (pintype "power_in"))
      (node (ref "IC2") (pin "4") (pinfunction "P$V-_4") (pintype "bidirectional"))
      (node (ref "IC3") (pin "4") (pinfunction "P$V-_4") (pintype "bidirectional"))
      (node (ref "IC4") (pin "4") (pinfunction "P$V-_4") (pintype "bidirectional"))
      (node (ref "IC5") (pin "4") (pinfunction "P$V-_4") (pintype "bidirectional"))
      (node (ref "IC6") (pin "4") (pinfunction "P$V-_4") (pintype "bidirectional"))
      (node (ref "L2") (pin "1") (pinfunction "1_1") (pintype "passive"))
      (node (ref "R16") (pin "2") (pinfunction "2_2") (pintype "passive"))
    )
    (net (code "59") (name "unconnected-(IC1C-CTRL-Pad11)") (class "Default")
      (node (ref "IC1") (pin "11") (pinfunction "CTRL_11") (pintype "input"))
    )
    (net (code "60") (name "unconnected-(IC1C-IN-Pad10)") (class "Default")
      (node (ref "IC1") (pin "10") (pinfunction "IN_10") (pintype "input"))
    )
    (net (code "61") (name "unconnected-(IC1C-OUT-Pad12)") (class "Default")
      (node (ref "IC1") (pin "12") (pinfunction "OUT_12") (pintype "output"))
    )
    (net (code "62") (name "unconnected-(IC1D-CTRL-Pad14)") (class "Default")
      (node (ref "IC1") (pin "14") (pinfunction "CTRL_14") (pintype "input"))
    )
    (net (code "63") (name "unconnected-(IC1D-IN-Pad15)") (class "Default")
      (node (ref "IC1") (pin "15") (pinfunction "IN_15") (pintype "input"))
    )
    (net (code "64") (name "unconnected-(IC1D-OUT-Pad13)") (class "Default")
      (node (ref "IC1") (pin "13") (pinfunction "OUT_13") (pintype "output"))
    )
    (net (code "65") (name "unconnected-(IC1E-MODE-Pad1)") (class "Default")
      (node (ref "IC1") (pin "1") (pinfunction "MODE_1") (pintype "input"))
    )
  )
)
